# Mag_Read_STM_IN.net
KiCad netlist of a schematic drawn in EAGLE
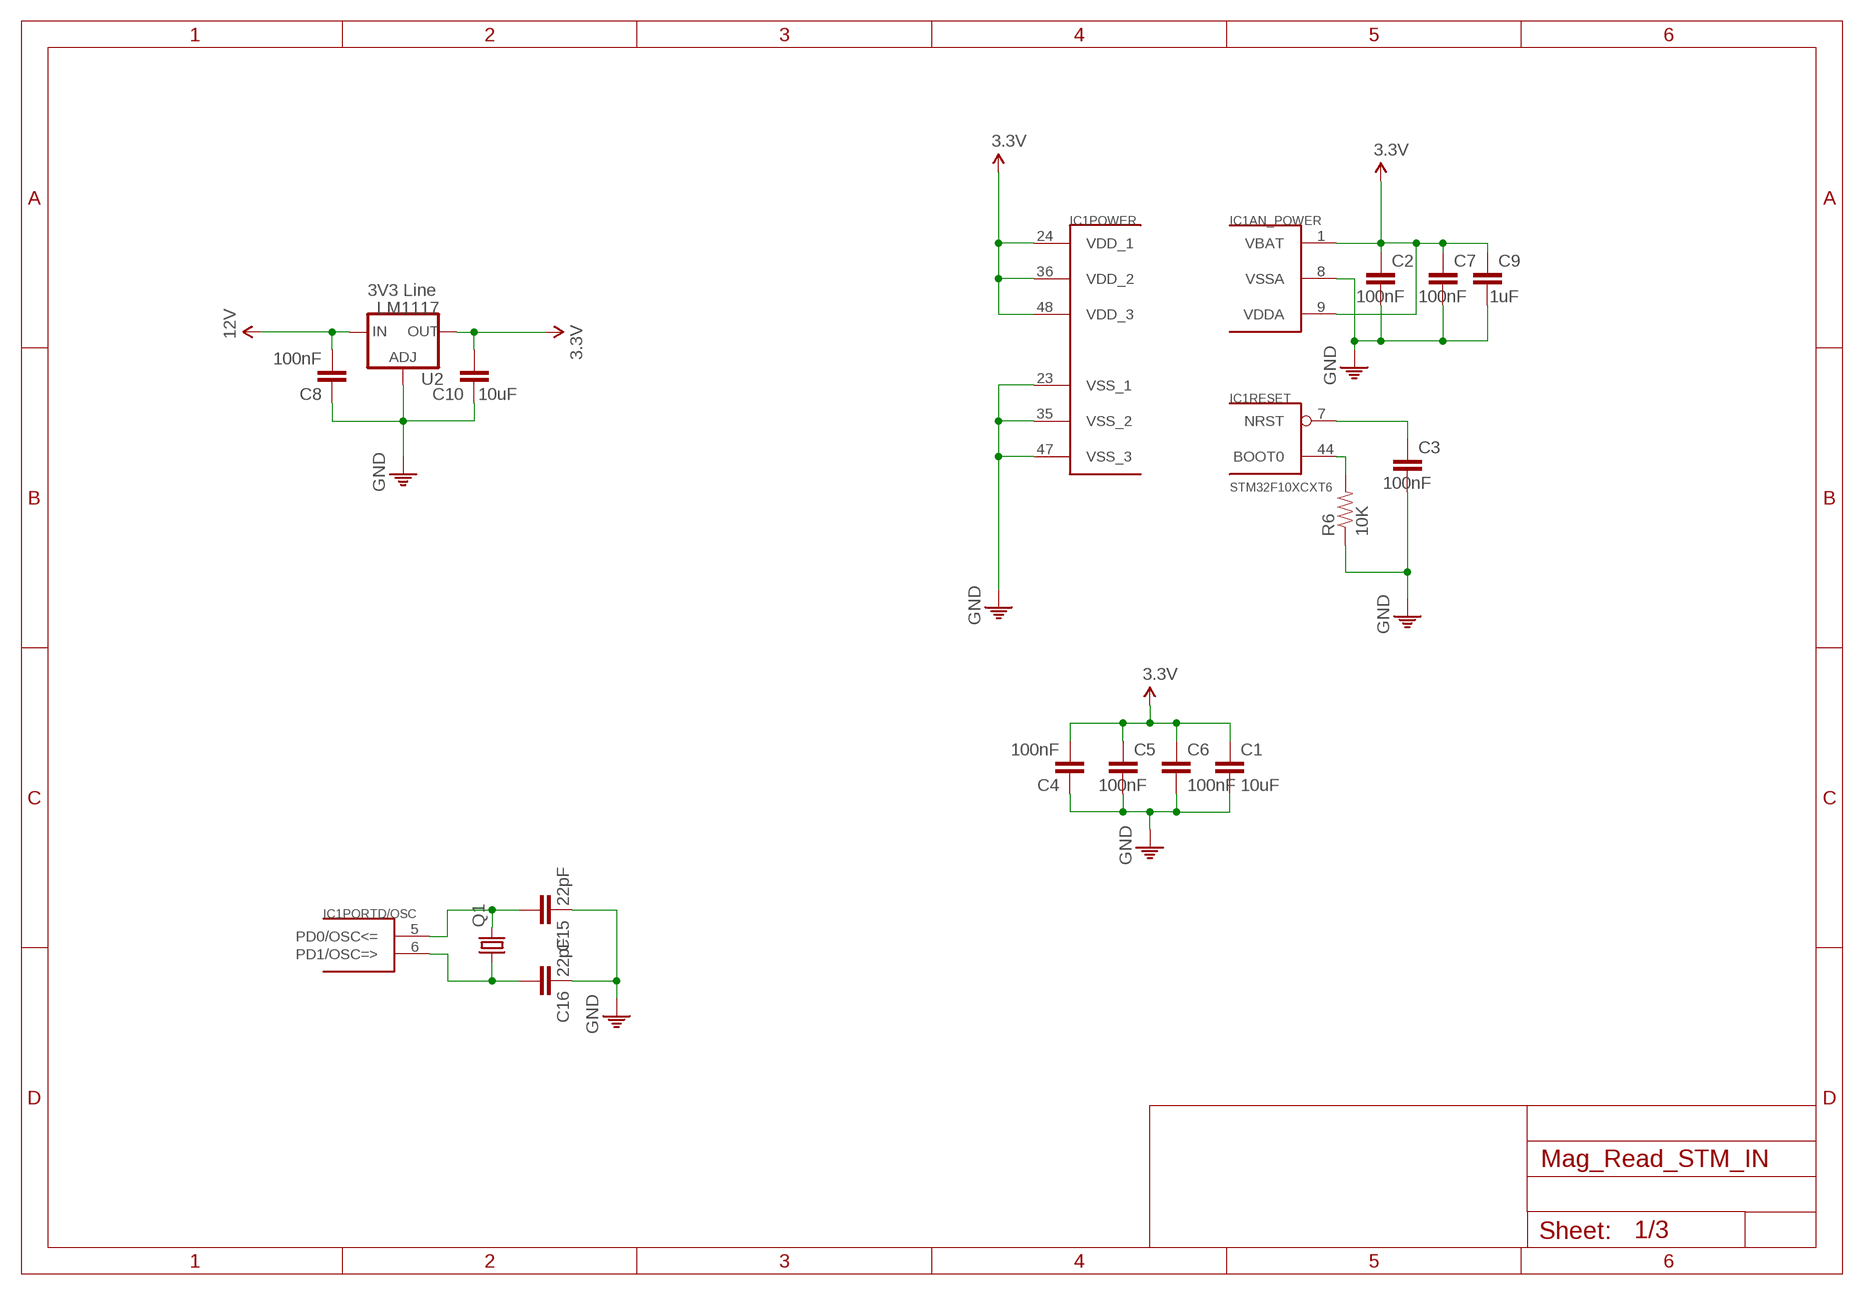
[diagram p0: schematic, sheet 1]
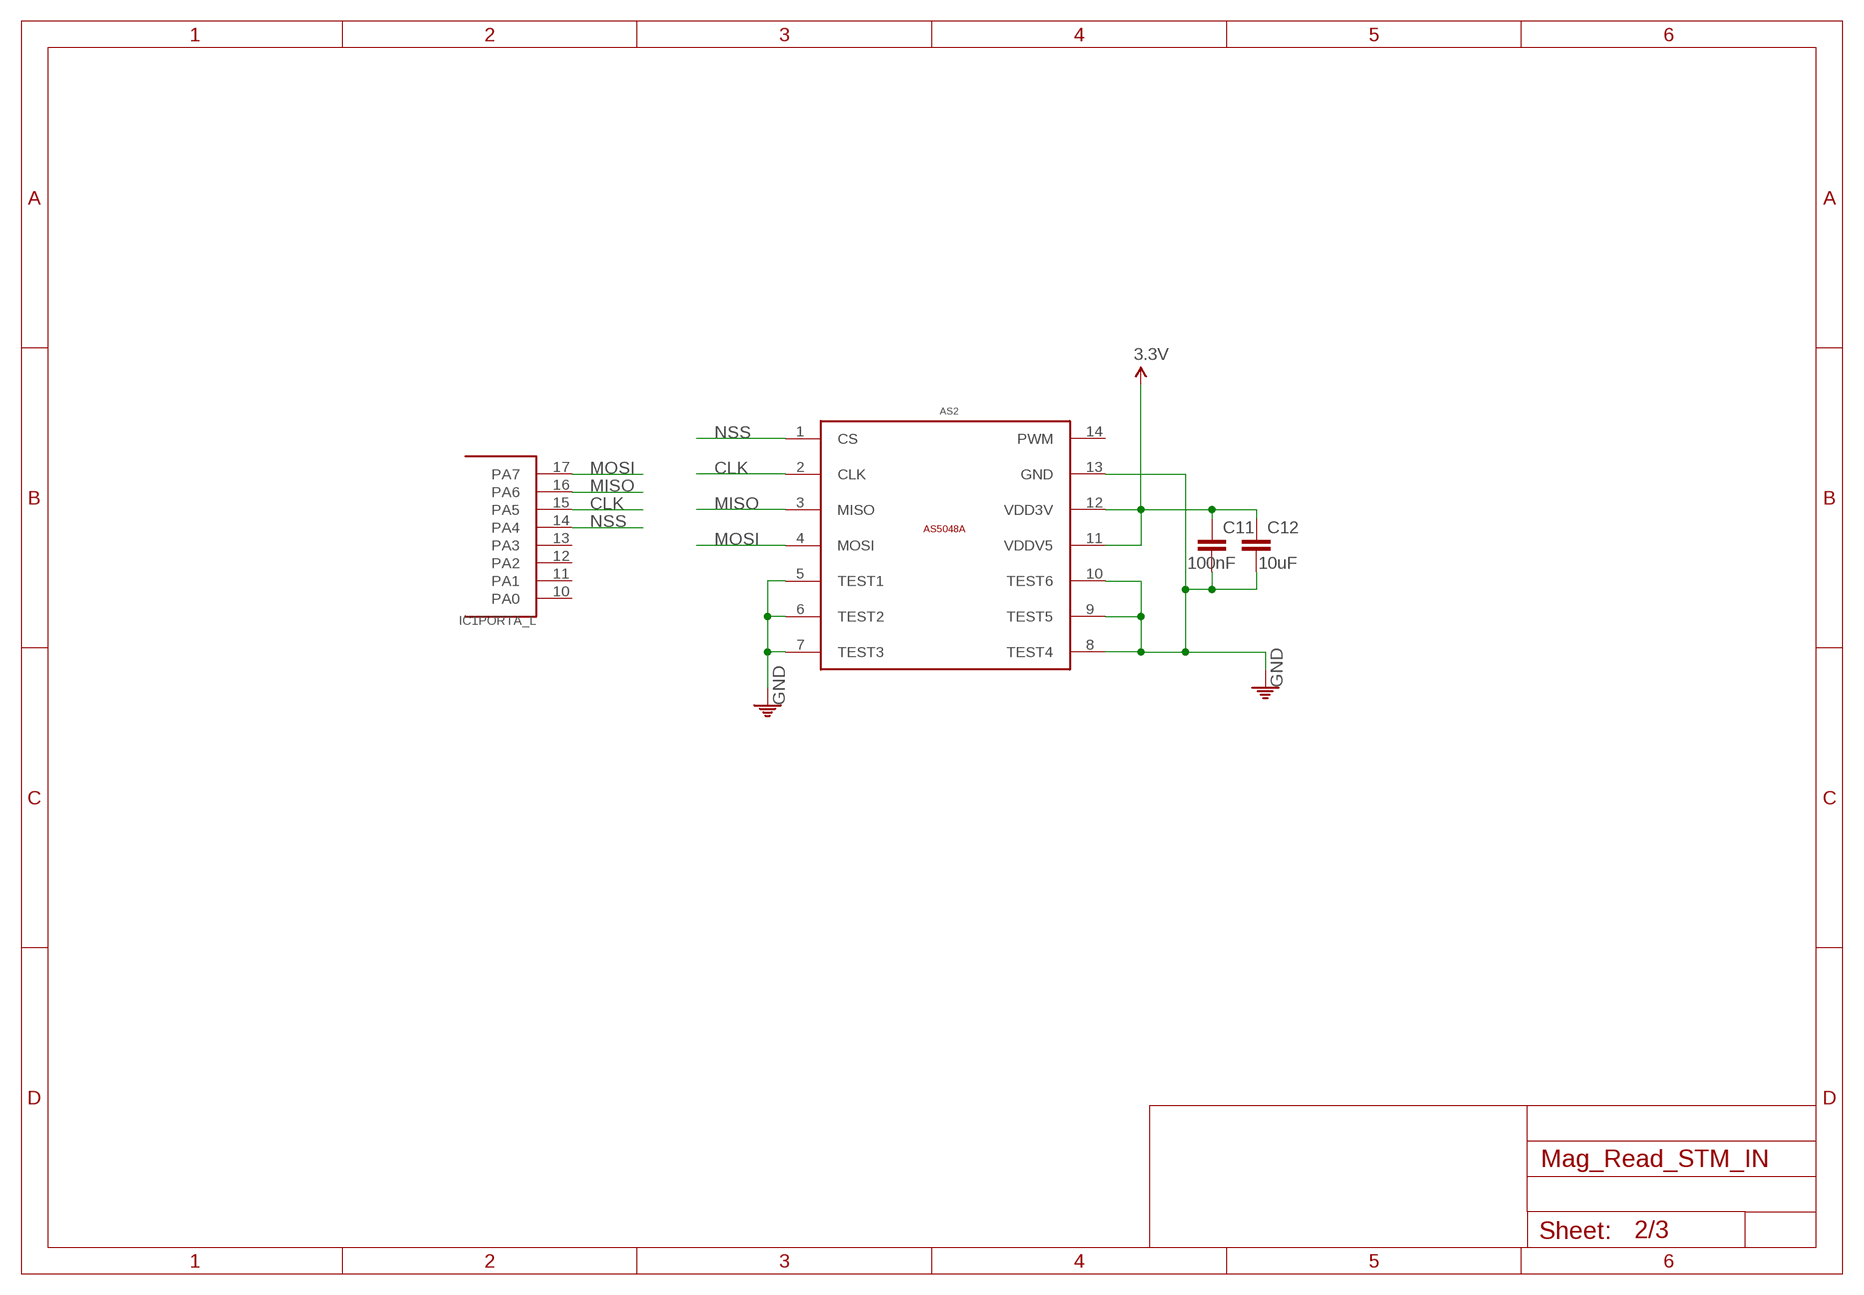
[diagram p1: schematic, sheet 2]
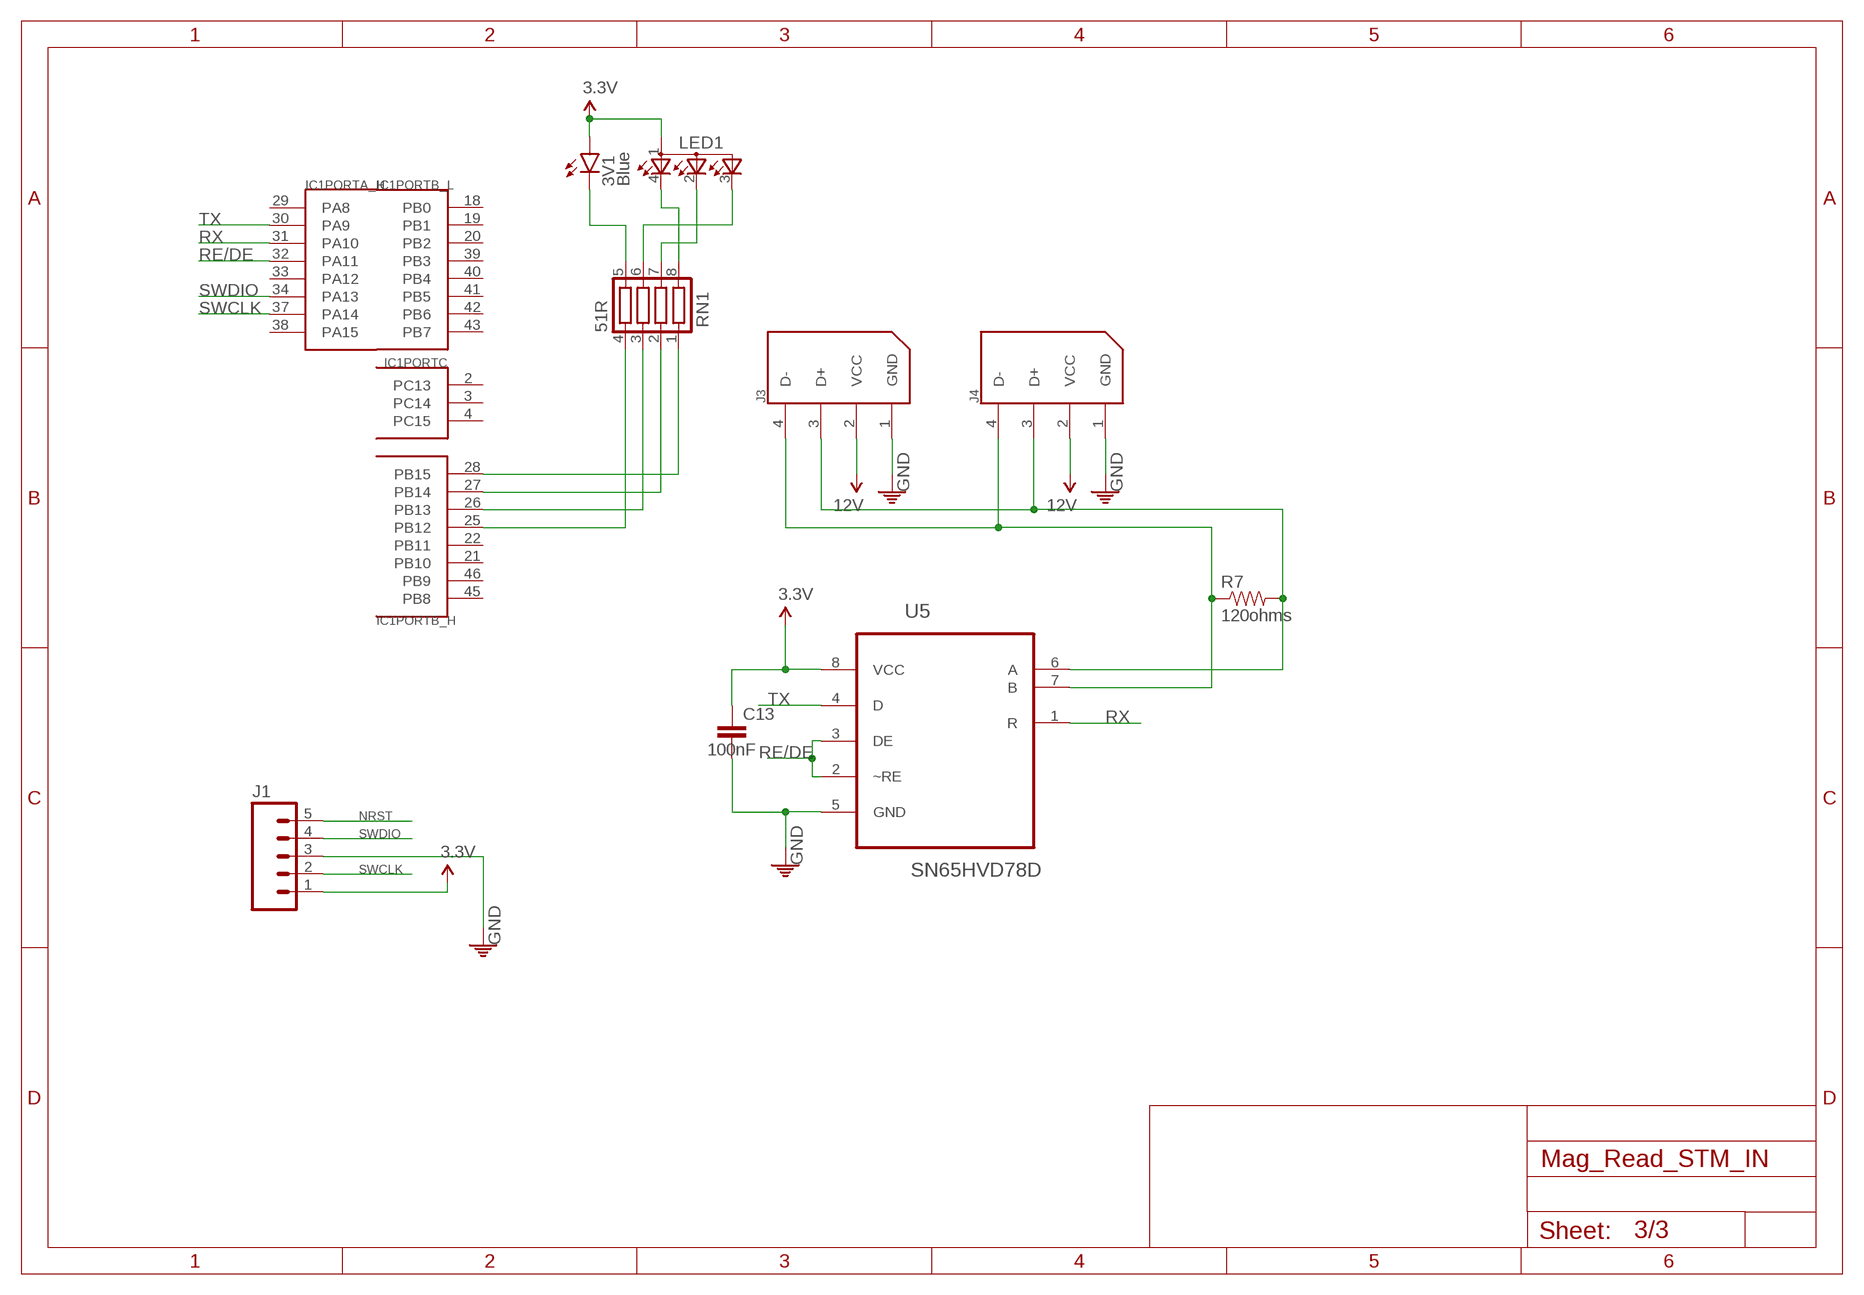
[diagram p2: schematic, sheet 3]

(export (version "E")
  (design (tool "Eeschema 10.0.6"))
  (components
    (comp (ref "C1")
      (value "10uF")
      (footprint "eagle-import:C0603")
      (libsource (lib "eagle-import") (part "C-EUC0603"))
    )
    (comp (ref "C2")
      (value "100nF")
      (footprint "eagle-import:C0603")
      (libsource (lib "eagle-import") (part "C-EUC0603"))
    )
    (comp (ref "C3")
      (value "100nF")
      (footprint "eagle-import:C0603")
      (libsource (lib "eagle-import") (part "C-EUC0603"))
    )
    (comp (ref "C4")
      (value "100nF")
      (footprint "eagle-import:C0603")
      (libsource (lib "eagle-import") (part "C-EUC0603"))
    )
    (comp (ref "C5")
      (value "100nF")
      (footprint "eagle-import:C0603")
      (libsource (lib "eagle-import") (part "C-EUC0603"))
    )
    (comp (ref "C6")
      (value "100nF")
      (footprint "eagle-import:C0603")
      (libsource (lib "eagle-import") (part "C-EUC0603"))
    )
    (comp (ref "C7")
      (value "100nF")
      (footprint "eagle-import:C0603")
      (libsource (lib "eagle-import") (part "C-EUC0603"))
    )
    (comp (ref "C8")
      (value "100nF")
      (footprint "eagle-import:C0603")
      (libsource (lib "eagle-import") (part "C-EUC0603"))
    )
    (comp (ref "C9")
      (value "1uF")
      (footprint "eagle-import:C0603")
      (libsource (lib "eagle-import") (part "C-EUC0603"))
    )
    (comp (ref "C10")
      (value "10uF")
      (footprint "eagle-import:C0603")
      (libsource (lib "eagle-import") (part "C-EUC0603"))
    )
    (comp (ref "C15")
      (value "22pF")
      (footprint "eagle-import:C0603")
      (libsource (lib "eagle-import") (part "C-EUC0603"))
    )
    (comp (ref "C16")
      (value "22pF")
      (footprint "eagle-import:C0603")
      (libsource (lib "eagle-import") (part "C-EUC0603"))
    )
    (comp (ref "IC1")
      (value "STM32F10XCXT6")
      (footprint "eagle-import:TQFP48")
      (libsource (lib "eagle-import") (part "STM32F10XCXT6"))
    )
    (comp (ref "Q1")
      (value "CRYSTALCTS406")
      (footprint "eagle-import:CTS406")
      (libsource (lib "eagle-import") (part "CRYSTALCTS406"))
    )
    (comp (ref "R6")
      (value "10K")
      (footprint "eagle-import:0603-RES")
      (libsource (lib "eagle-import") (part "RESISTOR0603-RES"))
    )
    (comp (ref "U2")
      (value "LM1117")
      (footprint "eagle-import:SOT223")
      (libsource (lib "eagle-import") (part "V_REG_317SMD"))
    )
    (comp (ref "AS2")
      (value "AS5048A_MAGNETIC_ROTARY_ENCODERTSSOP14")
      (footprint "eagle-import:AS5048A_14-TSSOP")
      (libsource (lib "eagle-import") (part "AS5048A_MAGNETIC_ROTARY_ENCODERTSSOP14"))
    )
    (comp (ref "C11")
      (value "100nF")
      (footprint "eagle-import:C0603")
      (libsource (lib "eagle-import") (part "C-EUC0603"))
    )
    (comp (ref "C12")
      (value "10uF")
      (footprint "eagle-import:C0603")
      (libsource (lib "eagle-import") (part "C-EUC0603"))
    )
    (comp (ref "3V1")
      (value "Blue")
      (footprint "eagle-import:LED-0603")
      (libsource (lib "eagle-import") (part "LED0603"))
    )
    (comp (ref "C13")
      (value "100nF")
      (footprint "eagle-import:C0603")
      (libsource (lib "eagle-import") (part "C-EUC0603"))
    )
    (comp (ref "J1")
      (value "M05PTH")
      (footprint "eagle-import:1X05")
      (libsource (lib "eagle-import") (part "M05PTH"))
    )
    (comp (ref "J3")
      (value "22-03-5045")
      (footprint "eagle-import:5267-4")
      (libsource (lib "eagle-import") (part "22-03-5045"))
    )
    (comp (ref "J4")
      (value "22-03-5045")
      (footprint "eagle-import:5267-4")
      (libsource (lib "eagle-import") (part "22-03-5045"))
    )
    (comp (ref "LED1")
      (value "TOPLED-3")
      (footprint "eagle-import:P-LCC-4-3")
      (libsource (lib "eagle-import") (part "TOPLED-3"))
    )
    (comp (ref "R7")
      (value "120ohms")
      (footprint "eagle-import:0603-RES")
      (libsource (lib "eagle-import") (part "RESISTOR0603-RES"))
    )
    (comp (ref "RN1")
      (value "51R")
      (footprint "eagle-import:CAY10-XXXJ4")
      (libsource (lib "eagle-import") (part "CAY10-XXXJ"))
    )
    (comp (ref "U5")
      (value "SN65HVD78D")
      (footprint "eagle-import:SOIC127P600X175-8N")
      (fields (field (name "MPN") "SN75176BD"))
      (libsource (lib "eagle-import") (part "SN75176BD"))
    )
  )
  (nets
    (net (code "1") (name "3.3V") (class "Default")
      (node (ref "3V1") (pin "A") (pinfunction "A_A") (pintype "passive"))
      (node (ref "AS2") (pin "11") (pinfunction "VDDV5_11") (pintype "bidirectional"))
      (node (ref "AS2") (pin "12") (pinfunction "VDD3V_12") (pintype "bidirectional"))
      (node (ref "C1") (pin "1") (pinfunction "1_1") (pintype "passive"))
      (node (ref "C10") (pin "2") (pinfunction "2_2") (pintype "passive"))
      (node (ref "C11") (pin "1") (pinfunction "1_1") (pintype "passive"))
      (node (ref "C12") (pin "1") (pinfunction "1_1") (pintype "passive"))
      (node (ref "C13") (pin "1") (pinfunction "1_1") (pintype "passive"))
      (node (ref "C2") (pin "1") (pinfunction "1_1") (pintype "passive"))
      (node (ref "C4") (pin "2") (pinfunction "2_2") (pintype "passive"))
      (node (ref "C5") (pin "1") (pinfunction "1_1") (pintype "passive"))
      (node (ref "C6") (pin "1") (pinfunction "1_1") (pintype "passive"))
      (node (ref "C7") (pin "1") (pinfunction "1_1") (pintype "passive"))
      (node (ref "C9") (pin "1") (pinfunction "1_1") (pintype "passive"))
      (node (ref "IC1") (pin "1") (pinfunction "VBAT_1") (pintype "power_in"))
      (node (ref "IC1") (pin "24") (pinfunction "VDD_1_24") (pintype "power_in"))
      (node (ref "IC1") (pin "36") (pinfunction "VDD_2_36") (pintype "power_in"))
      (node (ref "IC1") (pin "48") (pinfunction "VDD_3_48") (pintype "power_in"))
      (node (ref "IC1") (pin "9") (pinfunction "VDDA_9") (pintype "power_in"))
      (node (ref "J1") (pin "1") (pinfunction "1_1") (pintype "passive"))
      (node (ref "LED1") (pin "1") (pinfunction "A2_1") (pintype "passive"))
      (node (ref "U2") (pin "2") (pinfunction "OUT_2") (pintype "output"))
      (node (ref "U2") (pin "4") (pinfunction "OUT_4") (pintype "output"))
      (node (ref "U5") (pin "8") (pinfunction "VCC_8") (pintype "power_in"))
    )
    (net (code "2") (name "12V") (class "Default")
      (node (ref "C8") (pin "2") (pinfunction "2_2") (pintype "passive"))
      (node (ref "J3") (pin "2") (pinfunction "VCC_2") (pintype "bidirectional"))
      (node (ref "J4") (pin "2") (pinfunction "VCC_2") (pintype "bidirectional"))
      (node (ref "U2") (pin "3") (pinfunction "IN_3") (pintype "input"))
    )
    (net (code "3") (name "CLK") (class "Default")
      (node (ref "AS2") (pin "2") (pinfunction "CLK_2") (pintype "bidirectional"))
      (node (ref "IC1") (pin "15") (pinfunction "PA5_15") (pintype "bidirectional"))
    )
    (net (code "4") (name "GND") (class "Default")
      (node (ref "AS2") (pin "10") (pinfunction "TEST6_10") (pintype "bidirectional"))
      (node (ref "AS2") (pin "13") (pinfunction "GND_13") (pintype "bidirectional"))
      (node (ref "AS2") (pin "5") (pinfunction "TEST1_5") (pintype "bidirectional"))
      (node (ref "AS2") (pin "6") (pinfunction "TEST2_6") (pintype "bidirectional"))
      (node (ref "AS2") (pin "7") (pinfunction "TEST3_7") (pintype "bidirectional"))
      (node (ref "AS2") (pin "8") (pinfunction "TEST4_8") (pintype "bidirectional"))
      (node (ref "AS2") (pin "9") (pinfunction "TEST5_9") (pintype "bidirectional"))
      (node (ref "C1") (pin "2") (pinfunction "2_2") (pintype "passive"))
      (node (ref "C10") (pin "1") (pinfunction "1_1") (pintype "passive"))
      (node (ref "C11") (pin "2") (pinfunction "2_2") (pintype "passive"))
      (node (ref "C12") (pin "2") (pinfunction "2_2") (pintype "passive"))
      (node (ref "C13") (pin "2") (pinfunction "2_2") (pintype "passive"))
      (node (ref "C15") (pin "1") (pinfunction "1_1") (pintype "passive"))
      (node (ref "C16") (pin "1") (pinfunction "1_1") (pintype "passive"))
      (node (ref "C2") (pin "2") (pinfunction "2_2") (pintype "passive"))
      (node (ref "C3") (pin "2") (pinfunction "2_2") (pintype "passive"))
      (node (ref "C4") (pin "1") (pinfunction "1_1") (pintype "passive"))
      (node (ref "C5") (pin "2") (pinfunction "2_2") (pintype "passive"))
      (node (ref "C6") (pin "2") (pinfunction "2_2") (pintype "passive"))
      (node (ref "C7") (pin "2") (pinfunction "2_2") (pintype "passive"))
      (node (ref "C8") (pin "1") (pinfunction "1_1") (pintype "passive"))
      (node (ref "C9") (pin "2") (pinfunction "2_2") (pintype "passive"))
      (node (ref "IC1") (pin "23") (pinfunction "VSS_1_23") (pintype "power_in"))
      (node (ref "IC1") (pin "35") (pinfunction "VSS_2_35") (pintype "power_in"))
      (node (ref "IC1") (pin "47") (pinfunction "VSS_3_47") (pintype "power_in"))
      (node (ref "IC1") (pin "8") (pinfunction "VSSA_8") (pintype "power_in"))
      (node (ref "J1") (pin "3") (pinfunction "3_3") (pintype "passive"))
      (node (ref "J3") (pin "1") (pinfunction "GND_1") (pintype "bidirectional"))
      (node (ref "J4") (pin "1") (pinfunction "GND_1") (pintype "bidirectional"))
      (node (ref "R6") (pin "1") (pinfunction "1_1") (pintype "passive"))
      (node (ref "U2") (pin "1") (pinfunction "ADJ_1") (pintype "input"))
      (node (ref "U5") (pin "5") (pinfunction "GND_5") (pintype "passive"))
    )
    (net (code "5") (name "MISO") (class "Default")
      (node (ref "AS2") (pin "3") (pinfunction "MISO_3") (pintype "bidirectional"))
      (node (ref "IC1") (pin "16") (pinfunction "PA6_16") (pintype "bidirectional"))
    )
    (net (code "6") (name "MOSI") (class "Default")
      (node (ref "AS2") (pin "4") (pinfunction "MOSI_4") (pintype "bidirectional"))
      (node (ref "IC1") (pin "17") (pinfunction "PA7_17") (pintype "bidirectional"))
    )
    (net (code "7") (name "NRST") (class "Default")
      (node (ref "C3") (pin "1") (pinfunction "1_1") (pintype "passive"))
      (node (ref "IC1") (pin "7") (pinfunction "NRST_7") (pintype "input"))
      (node (ref "J1") (pin "5") (pinfunction "5_5") (pintype "passive"))
    )
    (net (code "8") (name "NSS") (class "Default")
      (node (ref "AS2") (pin "1") (pinfunction "CS_1") (pintype "bidirectional"))
      (node (ref "IC1") (pin "14") (pinfunction "PA4_14") (pintype "bidirectional"))
    )
    (net (code "9") (name "Net-(3V1-PadC)") (class "Default")
      (node (ref "3V1") (pin "C") (pinfunction "C_C") (pintype "passive"))
      (node (ref "RN1") (pin "5") (pinfunction "5_5") (pintype "passive"))
    )
    (net (code "10") (name "Net-(IC1D-PB12)") (class "Default")
      (node (ref "IC1") (pin "25") (pinfunction "PB12_25") (pintype "bidirectional"))
      (node (ref "RN1") (pin "4") (pinfunction "4_4") (pintype "passive"))
    )
    (net (code "11") (name "Net-(IC1D-PB13)") (class "Default")
      (node (ref "IC1") (pin "26") (pinfunction "PB13_26") (pintype "bidirectional"))
      (node (ref "RN1") (pin "3") (pinfunction "3_3") (pintype "passive"))
    )
    (net (code "12") (name "Net-(IC1D-PB14)") (class "Default")
      (node (ref "IC1") (pin "27") (pinfunction "PB14_27") (pintype "bidirectional"))
      (node (ref "RN1") (pin "2") (pinfunction "2_2") (pintype "passive"))
    )
    (net (code "13") (name "Net-(IC1D-PB15)") (class "Default")
      (node (ref "IC1") (pin "28") (pinfunction "PB15_28") (pintype "bidirectional"))
      (node (ref "RN1") (pin "1") (pinfunction "1_1") (pintype "passive"))
    )
    (net (code "14") (name "Net-(IC1G-PD0{slash}OSC<=)") (class "Default")
      (node (ref "C15") (pin "2") (pinfunction "2_2") (pintype "passive"))
      (node (ref "IC1") (pin "5") (pinfunction "PD0/OSC<=_5") (pintype "bidirectional"))
      (node (ref "Q1") (pin "3") (pinfunction "2_3") (pintype "passive"))
    )
    (net (code "15") (name "Net-(IC1G-PD1{slash}OSC=>)") (class "Default")
      (node (ref "C16") (pin "2") (pinfunction "2_2") (pintype "passive"))
      (node (ref "IC1") (pin "6") (pinfunction "PD1/OSC=>_6") (pintype "bidirectional"))
      (node (ref "Q1") (pin "1") (pinfunction "1_1") (pintype "passive"))
    )
    (net (code "16") (name "Net-(IC1I-BOOT0)") (class "Default")
      (node (ref "IC1") (pin "44") (pinfunction "BOOT0_44") (pintype "input"))
      (node (ref "R6") (pin "2") (pinfunction "2_2") (pintype "passive"))
    )
    (net (code "17") (name "Net-(J3-D+)") (class "Default")
      (node (ref "J3") (pin "3") (pinfunction "D+_3") (pintype "bidirectional"))
      (node (ref "J4") (pin "3") (pinfunction "D+_3") (pintype "bidirectional"))
      (node (ref "R7") (pin "2") (pinfunction "2_2") (pintype "passive"))
      (node (ref "U5") (pin "6") (pinfunction "A_6") (pintype "output"))
    )
    (net (code "18") (name "Net-(J3-D-)") (class "Default")
      (node (ref "J3") (pin "4") (pinfunction "D-_4") (pintype "bidirectional"))
      (node (ref "J4") (pin "4") (pinfunction "D-_4") (pintype "bidirectional"))
      (node (ref "R7") (pin "1") (pinfunction "1_1") (pintype "passive"))
      (node (ref "U5") (pin "7") (pinfunction "B_7") (pintype "output"))
    )
    (net (code "19") (name "Net-(LED1-CBLUE)") (class "Default")
      (node (ref "LED1") (pin "2") (pinfunction "CBLUE_2") (pintype "passive"))
      (node (ref "RN1") (pin "7") (pinfunction "7_7") (pintype "passive"))
    )
    (net (code "20") (name "Net-(LED1-CGREEN)") (class "Default")
      (node (ref "LED1") (pin "3") (pinfunction "CGREEN_3") (pintype "passive"))
      (node (ref "RN1") (pin "6") (pinfunction "6_6") (pintype "passive"))
    )
    (net (code "21") (name "Net-(LED1-CRED)") (class "Default")
      (node (ref "LED1") (pin "4") (pinfunction "CRED_4") (pintype "passive"))
      (node (ref "RN1") (pin "8") (pinfunction "8_8") (pintype "passive"))
    )
    (net (code "22") (name "RE{slash}DE") (class "Default")
      (node (ref "IC1") (pin "32") (pinfunction "PA11_32") (pintype "bidirectional"))
      (node (ref "U5") (pin "2") (pinfunction "~{RE}_2") (pintype "input"))
      (node (ref "U5") (pin "3") (pinfunction "DE_3") (pintype "input"))
    )
    (net (code "23") (name "RX") (class "Default")
      (node (ref "IC1") (pin "31") (pinfunction "PA10_31") (pintype "bidirectional"))
      (node (ref "U5") (pin "1") (pinfunction "R_1") (pintype "output"))
    )
    (net (code "24") (name "SWCLK") (class "Default")
      (node (ref "IC1") (pin "37") (pinfunction "PA14_37") (pintype "bidirectional"))
      (node (ref "J1") (pin "2") (pinfunction "2_2") (pintype "passive"))
    )
    (net (code "25") (name "SWDIO") (class "Default")
      (node (ref "IC1") (pin "34") (pinfunction "PA13_34") (pintype "bidirectional"))
      (node (ref "J1") (pin "4") (pinfunction "4_4") (pintype "passive"))
    )
    (net (code "26") (name "TX") (class "Default")
      (node (ref "IC1") (pin "30") (pinfunction "PA9_30") (pintype "bidirectional"))
      (node (ref "U5") (pin "4") (pinfunction "D_4") (pintype "input"))
    )
    (net (code "27") (name "unconnected-(AS2-PWM-Pad14)") (class "Default")
      (node (ref "AS2") (pin "14") (pinfunction "PWM_14") (pintype "bidirectional"))
    )
    (net (code "28") (name "unconnected-(IC1B-PA8-Pad29)") (class "Default")
      (node (ref "IC1") (pin "29") (pinfunction "PA8_29") (pintype "bidirectional"))
    )
    (net (code "29") (name "unconnected-(IC1B-PA12-Pad33)") (class "Default")
      (node (ref "IC1") (pin "33") (pinfunction "PA12_33") (pintype "bidirectional"))
    )
    (net (code "30") (name "unconnected-(IC1B-PA15-Pad38)") (class "Default")
      (node (ref "IC1") (pin "38") (pinfunction "PA15_38") (pintype "bidirectional"))
    )
    (net (code "31") (name "unconnected-(IC1C-PA0-Pad10)") (class "Default")
      (node (ref "IC1") (pin "10") (pinfunction "PA0_10") (pintype "bidirectional"))
    )
    (net (code "32") (name "unconnected-(IC1C-PA1-Pad11)") (class "Default")
      (node (ref "IC1") (pin "11") (pinfunction "PA1_11") (pintype "bidirectional"))
    )
    (net (code "33") (name "unconnected-(IC1C-PA2-Pad12)") (class "Default")
      (node (ref "IC1") (pin "12") (pinfunction "PA2_12") (pintype "bidirectional"))
    )
    (net (code "34") (name "unconnected-(IC1C-PA3-Pad13)") (class "Default")
      (node (ref "IC1") (pin "13") (pinfunction "PA3_13") (pintype "bidirectional"))
    )
    (net (code "35") (name "unconnected-(IC1D-PB8-Pad45)") (class "Default")
      (node (ref "IC1") (pin "45") (pinfunction "PB8_45") (pintype "bidirectional"))
    )
    (net (code "36") (name "unconnected-(IC1D-PB9-Pad46)") (class "Default")
      (node (ref "IC1") (pin "46") (pinfunction "PB9_46") (pintype "bidirectional"))
    )
    (net (code "37") (name "unconnected-(IC1D-PB10-Pad21)") (class "Default")
      (node (ref "IC1") (pin "21") (pinfunction "PB10_21") (pintype "bidirectional"))
    )
    (net (code "38") (name "unconnected-(IC1D-PB11-Pad22)") (class "Default")
      (node (ref "IC1") (pin "22") (pinfunction "PB11_22") (pintype "bidirectional"))
    )
    (net (code "39") (name "unconnected-(IC1E-PB0-Pad18)") (class "Default")
      (node (ref "IC1") (pin "18") (pinfunction "PB0_18") (pintype "bidirectional"))
    )
    (net (code "40") (name "unconnected-(IC1E-PB1-Pad19)") (class "Default")
      (node (ref "IC1") (pin "19") (pinfunction "PB1_19") (pintype "bidirectional"))
    )
    (net (code "41") (name "unconnected-(IC1E-PB2-Pad20)") (class "Default")
      (node (ref "IC1") (pin "20") (pinfunction "PB2_20") (pintype "bidirectional"))
    )
    (net (code "42") (name "unconnected-(IC1E-PB3-Pad39)") (class "Default")
      (node (ref "IC1") (pin "39") (pinfunction "PB3_39") (pintype "bidirectional"))
    )
    (net (code "43") (name "unconnected-(IC1E-PB4-Pad40)") (class "Default")
      (node (ref "IC1") (pin "40") (pinfunction "PB4_40") (pintype "bidirectional"))
    )
    (net (code "44") (name "unconnected-(IC1E-PB5-Pad41)") (class "Default")
      (node (ref "IC1") (pin "41") (pinfunction "PB5_41") (pintype "bidirectional"))
    )
    (net (code "45") (name "unconnected-(IC1E-PB6-Pad42)") (class "Default")
      (node (ref "IC1") (pin "42") (pinfunction "PB6_42") (pintype "bidirectional"))
    )
    (net (code "46") (name "unconnected-(IC1E-PB7-Pad43)") (class "Default")
      (node (ref "IC1") (pin "43") (pinfunction "PB7_43") (pintype "bidirectional"))
    )
    (net (code "47") (name "unconnected-(IC1F-PC13-Pad2)") (class "Default")
      (node (ref "IC1") (pin "2") (pinfunction "PC13_2") (pintype "bidirectional"))
    )
    (net (code "48") (name "unconnected-(IC1F-PC14-Pad3)") (class "Default")
      (node (ref "IC1") (pin "3") (pinfunction "PC14_3") (pintype "bidirectional"))
    )
    (net (code "49") (name "unconnected-(IC1F-PC15-Pad4)") (class "Default")
      (node (ref "IC1") (pin "4") (pinfunction "PC15_4") (pintype "bidirectional"))
    )
  )
)
